# LoRa_SX1276_Shield.net
KiCad netlist of a schematic drawn in EAGLE
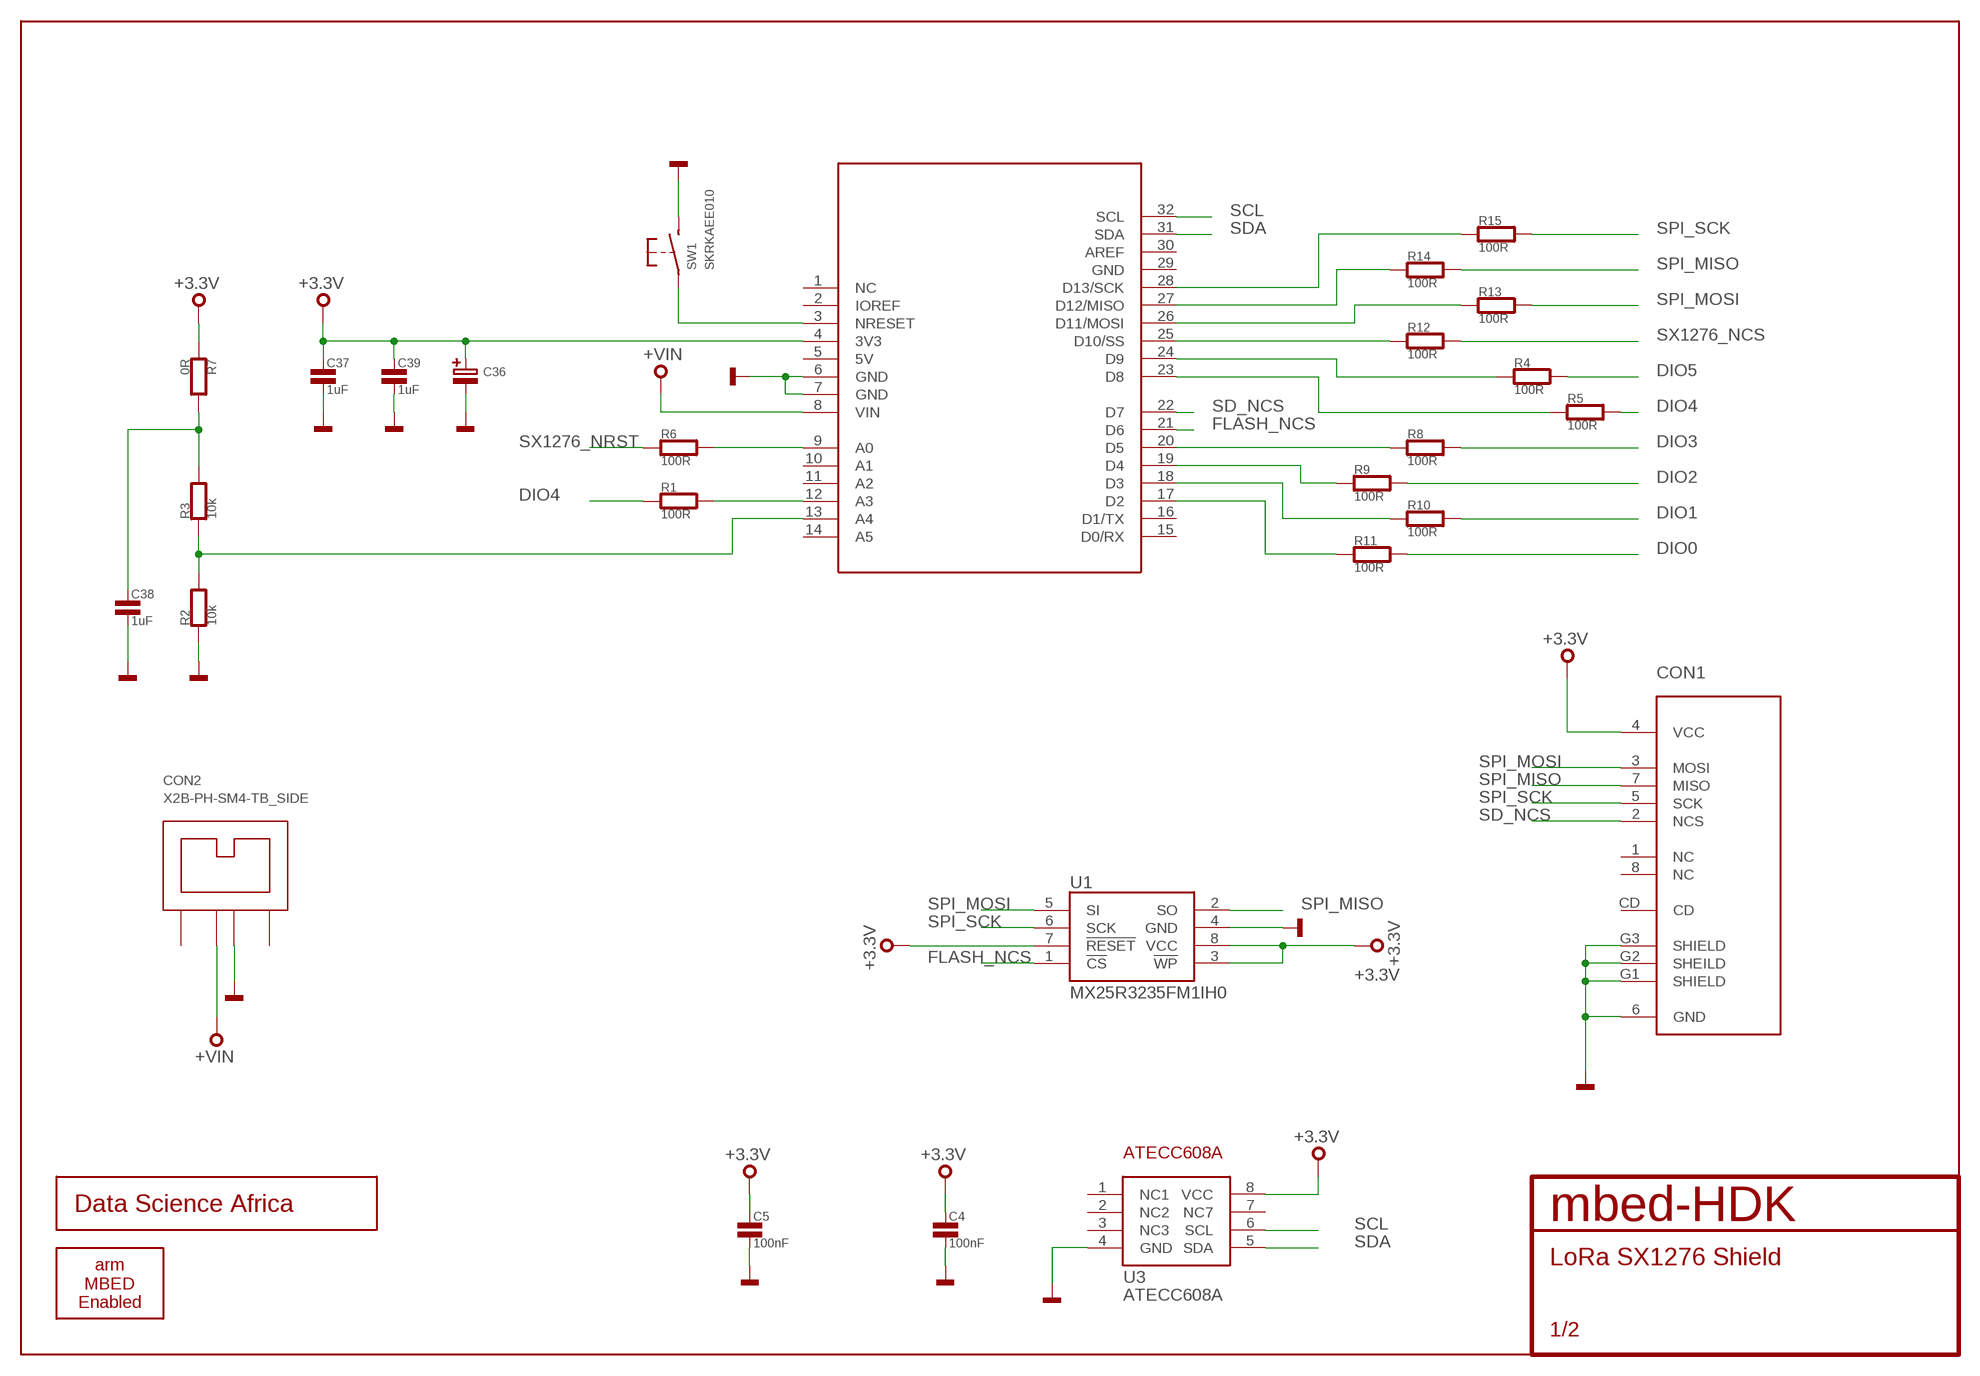
[diagram p0: schematic, sheet 1]
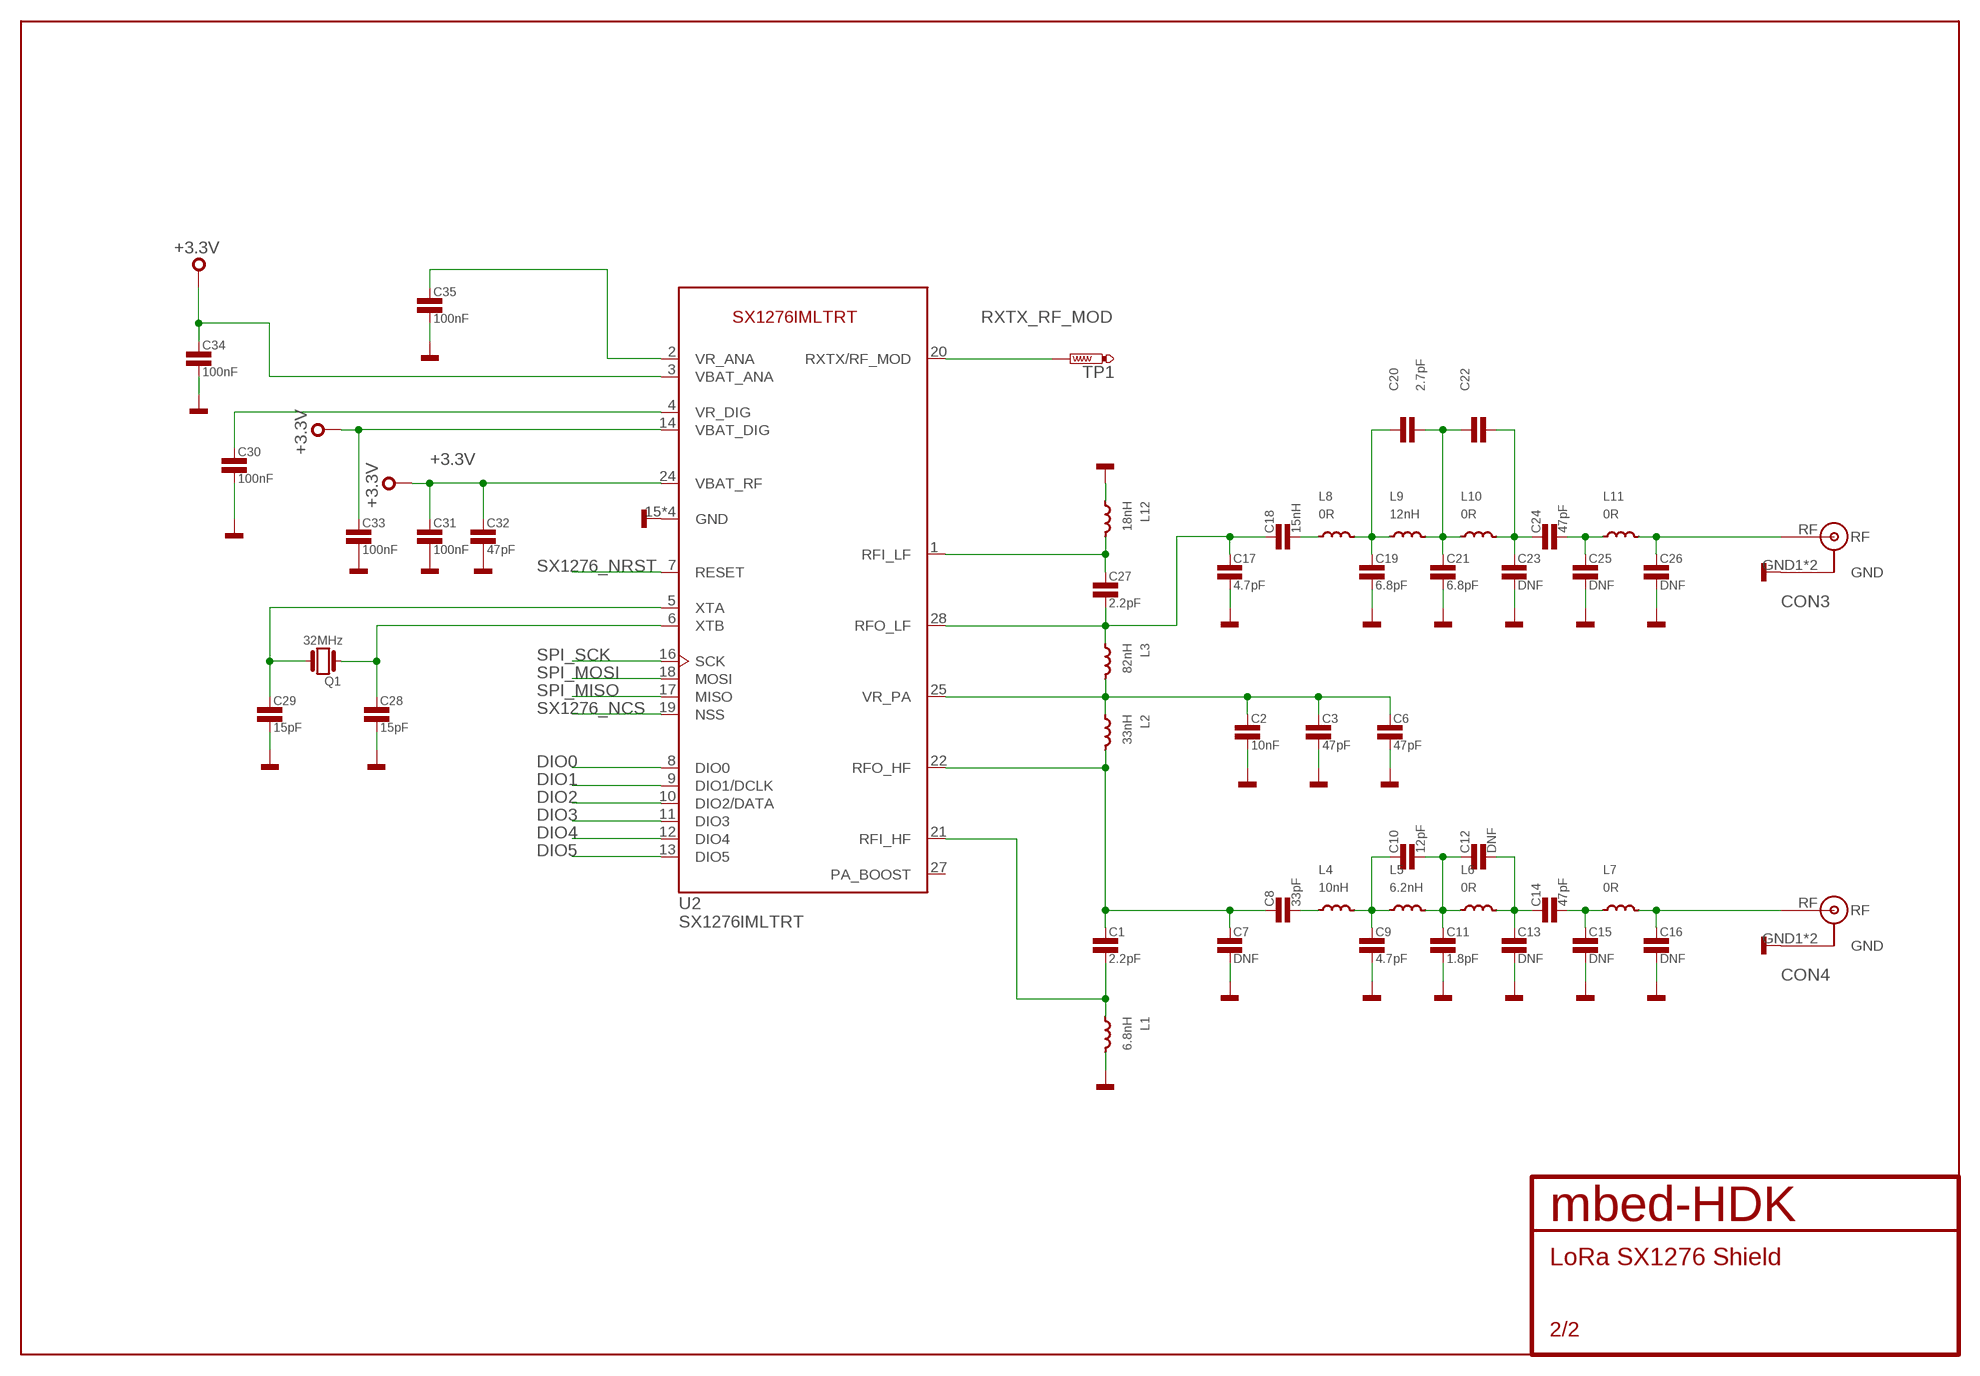
[diagram p1: schematic, sheet 2]

(export (version "E")
  (design (tool "Eeschema 10.0.6"))
  (components
    (comp (ref "C1")
      (value "2.2pF")
      (footprint "eagle-import:0402")
      (libsource (lib "eagle-import") (part "C0402"))
    )
    (comp (ref "C2")
      (value "10nF")
      (footprint "eagle-import:0402")
      (libsource (lib "eagle-import") (part "C0402"))
    )
    (comp (ref "C3")
      (value "47pF")
      (footprint "eagle-import:0402")
      (libsource (lib "eagle-import") (part "C0402"))
    )
    (comp (ref "C6")
      (value "47pF")
      (footprint "eagle-import:0402")
      (libsource (lib "eagle-import") (part "C0402"))
    )
    (comp (ref "C7")
      (value "DNF")
      (footprint "eagle-import:0402")
      (libsource (lib "eagle-import") (part "C0402"))
    )
    (comp (ref "C8")
      (value "33pF")
      (footprint "eagle-import:0402")
      (libsource (lib "eagle-import") (part "C0402"))
    )
    (comp (ref "C9")
      (value "4.7pF")
      (footprint "eagle-import:0402")
      (libsource (lib "eagle-import") (part "C0402"))
    )
    (comp (ref "C10")
      (value "12pF")
      (footprint "eagle-import:0402")
      (libsource (lib "eagle-import") (part "C0402"))
    )
    (comp (ref "C11")
      (value "1.8pF")
      (footprint "eagle-import:0402")
      (libsource (lib "eagle-import") (part "C0402"))
    )
    (comp (ref "C12")
      (value "DNF")
      (footprint "eagle-import:0402")
      (libsource (lib "eagle-import") (part "C0402"))
    )
    (comp (ref "C13")
      (value "DNF")
      (footprint "eagle-import:0402")
      (libsource (lib "eagle-import") (part "C0402"))
    )
    (comp (ref "C14")
      (value "47pF")
      (footprint "eagle-import:0402")
      (libsource (lib "eagle-import") (part "C0402"))
    )
    (comp (ref "C15")
      (value "DNF")
      (footprint "eagle-import:0402")
      (libsource (lib "eagle-import") (part "C0402"))
    )
    (comp (ref "C16")
      (value "DNF")
      (footprint "eagle-import:0402")
      (libsource (lib "eagle-import") (part "C0402"))
    )
    (comp (ref "C17")
      (value "4.7pF")
      (footprint "eagle-import:0402")
      (libsource (lib "eagle-import") (part "C0402"))
    )
    (comp (ref "C18")
      (value "15nH")
      (footprint "eagle-import:0402")
      (libsource (lib "eagle-import") (part "C0402"))
    )
    (comp (ref "C19")
      (value "6.8pF")
      (footprint "eagle-import:0402")
      (libsource (lib "eagle-import") (part "C0402"))
    )
    (comp (ref "C20")
      (value "2.7pF")
      (footprint "eagle-import:0402")
      (libsource (lib "eagle-import") (part "C0402"))
    )
    (comp (ref "C21")
      (value "6.8pF")
      (footprint "eagle-import:0402")
      (libsource (lib "eagle-import") (part "C0402"))
    )
    (comp (ref "C22")
      (value "C0402")
      (footprint "eagle-import:0402")
      (libsource (lib "eagle-import") (part "C0402"))
    )
    (comp (ref "C23")
      (value "DNF")
      (footprint "eagle-import:0402")
      (libsource (lib "eagle-import") (part "C0402"))
    )
    (comp (ref "C24")
      (value "47pF")
      (footprint "eagle-import:0402")
      (libsource (lib "eagle-import") (part "C0402"))
    )
    (comp (ref "C25")
      (value "DNF")
      (footprint "eagle-import:0402")
      (libsource (lib "eagle-import") (part "C0402"))
    )
    (comp (ref "C26")
      (value "DNF")
      (footprint "eagle-import:0402")
      (libsource (lib "eagle-import") (part "C0402"))
    )
    (comp (ref "C27")
      (value "2.2pF")
      (footprint "eagle-import:0402")
      (libsource (lib "eagle-import") (part "C0402"))
    )
    (comp (ref "C28")
      (value "15pF")
      (footprint "eagle-import:0402")
      (libsource (lib "eagle-import") (part "C0402"))
    )
    (comp (ref "C29")
      (value "15pF")
      (footprint "eagle-import:0402")
      (libsource (lib "eagle-import") (part "C0402"))
    )
    (comp (ref "C30")
      (value "100nF")
      (footprint "eagle-import:0402")
      (libsource (lib "eagle-import") (part "C0402"))
    )
    (comp (ref "C31")
      (value "100nF")
      (footprint "eagle-import:0402")
      (libsource (lib "eagle-import") (part "C0402"))
    )
    (comp (ref "C32")
      (value "47pF")
      (footprint "eagle-import:0402")
      (libsource (lib "eagle-import") (part "C0402"))
    )
    (comp (ref "C33")
      (value "100nF")
      (footprint "eagle-import:0402")
      (libsource (lib "eagle-import") (part "C0402"))
    )
    (comp (ref "C34")
      (value "100nF")
      (footprint "eagle-import:0402")
      (libsource (lib "eagle-import") (part "C0402"))
    )
    (comp (ref "C35")
      (value "100nF")
      (footprint "eagle-import:0402")
      (libsource (lib "eagle-import") (part "C0402"))
    )
    (comp (ref "CON3")
      (value "U.FL")
      (footprint "eagle-import:U.FL-R-SMT-1")
      (libsource (lib "eagle-import") (part "U.FL"))
    )
    (comp (ref "CON4")
      (value "U.FL")
      (footprint "eagle-import:U.FL-R-SMT-1")
      (libsource (lib "eagle-import") (part "U.FL"))
    )
    (comp (ref "L1")
      (value "6.8nH")
      (footprint "eagle-import:0402")
      (libsource (lib "eagle-import") (part "L0402"))
    )
    (comp (ref "L2")
      (value "33nH")
      (footprint "eagle-import:0402")
      (libsource (lib "eagle-import") (part "L0402"))
    )
    (comp (ref "L3")
      (value "82nH")
      (footprint "eagle-import:0402")
      (libsource (lib "eagle-import") (part "L0402"))
    )
    (comp (ref "L4")
      (value "10nH")
      (footprint "eagle-import:0402")
      (libsource (lib "eagle-import") (part "L0402"))
    )
    (comp (ref "L5")
      (value "6.2nH")
      (footprint "eagle-import:0402")
      (libsource (lib "eagle-import") (part "L0402"))
    )
    (comp (ref "L6")
      (value "0R")
      (footprint "eagle-import:0402")
      (libsource (lib "eagle-import") (part "L0402"))
    )
    (comp (ref "L7")
      (value "0R")
      (footprint "eagle-import:0402")
      (libsource (lib "eagle-import") (part "L0402"))
    )
    (comp (ref "L8")
      (value "0R")
      (footprint "eagle-import:0402")
      (libsource (lib "eagle-import") (part "L0402"))
    )
    (comp (ref "L9")
      (value "12nH")
      (footprint "eagle-import:0402")
      (libsource (lib "eagle-import") (part "L0402"))
    )
    (comp (ref "L10")
      (value "0R")
      (footprint "eagle-import:0402")
      (libsource (lib "eagle-import") (part "L0402"))
    )
    (comp (ref "L11")
      (value "0R")
      (footprint "eagle-import:0402")
      (libsource (lib "eagle-import") (part "L0402"))
    )
    (comp (ref "L12")
      (value "18nH")
      (footprint "eagle-import:0402")
      (libsource (lib "eagle-import") (part "L0402"))
    )
    (comp (ref "Q1")
      (value "32MHz")
      (footprint "eagle-import:3.2X.2.5")
      (libsource (lib "eagle-import") (part "GENERIC-CRYSTAL_3.2X2.5"))
    )
    (comp (ref "TP1")
      (value "PTR1TP12R")
      (footprint "eagle-import:TP12R")
      (libsource (lib "eagle-import") (part "PTR1TP12R"))
    )
    (comp (ref "U2")
      (value "SX1276IMLTRT")
      (footprint "eagle-import:QFN65P600X600X100-29N")
      (fields (field (name "MF") "Semtec"))
      (libsource (lib "eagle-import") (part "SX1276IMLTRT"))
    )
    (comp (ref "BRD2")
      (value "ARDUINO-R3_APPS")
      (footprint "eagle-import:ARDUINO-R3-APPS-SHEILD")
      (libsource (lib "eagle-import") (part "ARDUINO-R3_APPS"))
    )
    (comp (ref "C4")
      (value "100nF")
      (footprint "eagle-import:0402")
      (libsource (lib "eagle-import") (part "C0402"))
    )
    (comp (ref "C5")
      (value "100nF")
      (footprint "eagle-import:0402")
      (libsource (lib "eagle-import") (part "C0402"))
    )
    (comp (ref "C36")
      (value "C-POLB")
      (footprint "eagle-import:SMC_B")
      (fields (field (name "MF") "Kemet"))
      (libsource (lib "eagle-import") (part "C-POLB"))
    )
    (comp (ref "C37")
      (value "1uF")
      (footprint "eagle-import:0603")
      (libsource (lib "eagle-import") (part "C0603"))
    )
    (comp (ref "C38")
      (value "1uF")
      (footprint "eagle-import:0603")
      (libsource (lib "eagle-import") (part "C0603"))
    )
    (comp (ref "C39")
      (value "1uF")
      (footprint "eagle-import:0402")
      (libsource (lib "eagle-import") (part "C0402"))
    )
    (comp (ref "CON1")
      (value "101-00660-68-6")
      (footprint "eagle-import:AMPHENOL-101-00660-68-6")
      (fields (field (name "MF") "Amphenol "))
      (libsource (lib "eagle-import") (part "101-00660-68-6"))
    )
    (comp (ref "CON2")
      (value "X2B-PH-SM4-TB_SIDE")
      (footprint "eagle-import:S2B-PH-SM4-TB")
      (libsource (lib "eagle-import") (part "X2B-PH-SM4-TB_SIDE"))
    )
    (comp (ref "R1")
      (value "100R")
      (footprint "eagle-import:0402")
      (libsource (lib "eagle-import") (part "R0402"))
    )
    (comp (ref "R2")
      (value "10k")
      (footprint "eagle-import:0402")
      (libsource (lib "eagle-import") (part "R0402"))
    )
    (comp (ref "R3")
      (value "10k")
      (footprint "eagle-import:0402")
      (libsource (lib "eagle-import") (part "R0402"))
    )
    (comp (ref "R4")
      (value "100R")
      (footprint "eagle-import:0402")
      (libsource (lib "eagle-import") (part "R0402"))
    )
    (comp (ref "R5")
      (value "100R")
      (footprint "eagle-import:0402")
      (libsource (lib "eagle-import") (part "R0402"))
    )
    (comp (ref "R6")
      (value "100R")
      (footprint "eagle-import:0402")
      (libsource (lib "eagle-import") (part "R0402"))
    )
    (comp (ref "R7")
      (value "0R")
      (footprint "eagle-import:0402")
      (libsource (lib "eagle-import") (part "R0402"))
    )
    (comp (ref "R8")
      (value "100R")
      (footprint "eagle-import:0402")
      (libsource (lib "eagle-import") (part "R0402"))
    )
    (comp (ref "R9")
      (value "100R")
      (footprint "eagle-import:0402")
      (libsource (lib "eagle-import") (part "R0402"))
    )
    (comp (ref "R10")
      (value "100R")
      (footprint "eagle-import:0402")
      (libsource (lib "eagle-import") (part "R0402"))
    )
    (comp (ref "R11")
      (value "100R")
      (footprint "eagle-import:0402")
      (libsource (lib "eagle-import") (part "R0402"))
    )
    (comp (ref "R12")
      (value "100R")
      (footprint "eagle-import:0402")
      (libsource (lib "eagle-import") (part "R0402"))
    )
    (comp (ref "R13")
      (value "100R")
      (footprint "eagle-import:0402")
      (libsource (lib "eagle-import") (part "R0402"))
    )
    (comp (ref "R14")
      (value "100R")
      (footprint "eagle-import:0402")
      (libsource (lib "eagle-import") (part "R0402"))
    )
    (comp (ref "R15")
      (value "100R")
      (footprint "eagle-import:0402")
      (libsource (lib "eagle-import") (part "R0402"))
    )
    (comp (ref "SS1")
      (value "ARM-MBED-ENABLED-12MM")
      (footprint "eagle-import:ARM-MBED-ENABLED-12MM")
      (libsource (lib "eagle-import") (part "ARM-MBED-ENABLED-12MM"))
    )
    (comp (ref "SS2")
      (value "DATA-SCIENCE-AFRICA")
      (footprint "eagle-import:DATA-SCIENCE-AFRICA")
      (libsource (lib "eagle-import") (part "DATA-SCIENCE-AFRICA"))
    )
    (comp (ref "SW1")
      (value "SKRKAEE010")
      (footprint "eagle-import:SKRKAEE010")
      (fields (field (name "MF") "ALPS"))
      (libsource (lib "eagle-import") (part "SKRKAEE010"))
    )
    (comp (ref "U1")
      (value "MX25R3235FM1IH0")
      (footprint "eagle-import:SO8")
      (fields (field (name "MF") "Macronix"))
      (libsource (lib "eagle-import") (part "MX25R3235FM1IH0"))
    )
    (comp (ref "U3")
      (value "ATECC608A")
      (footprint "eagle-import:SO8")
      (libsource (lib "eagle-import") (part "ATECC608A"))
    )
  )
  (nets
    (net (code "1") (name "+3.3V") (class "Default")
      (node (ref "BRD2") (pin "4") (pinfunction "3V3_4") (pintype "bidirectional"))
      (node (ref "C31") (pin "1") (pinfunction "P$1_1") (pintype "passive"))
      (node (ref "C32") (pin "1") (pinfunction "P$1_1") (pintype "passive"))
      (node (ref "C33") (pin "1") (pinfunction "P$1_1") (pintype "passive"))
      (node (ref "C34") (pin "1") (pinfunction "P$1_1") (pintype "passive"))
      (node (ref "C36") (pin "+") (pinfunction "+_+") (pintype "passive"))
      (node (ref "C37") (pin "1") (pinfunction "P$1_1") (pintype "passive"))
      (node (ref "C39") (pin "1") (pinfunction "P$1_1") (pintype "passive"))
      (node (ref "C4") (pin "1") (pinfunction "P$1_1") (pintype "passive"))
      (node (ref "C5") (pin "1") (pinfunction "P$1_1") (pintype "passive"))
      (node (ref "CON1") (pin "4") (pinfunction "VCC_4") (pintype "bidirectional"))
      (node (ref "R7") (pin "1") (pinfunction "P$1_1") (pintype "passive"))
      (node (ref "U1") (pin "3") (pinfunction "~{WP}_3") (pintype "bidirectional"))
      (node (ref "U1") (pin "7") (pinfunction "~{RESET}_7") (pintype "bidirectional"))
      (node (ref "U1") (pin "8") (pinfunction "VCC_8") (pintype "bidirectional"))
      (node (ref "U2") (pin "14") (pinfunction "VBAT_DIG_14") (pintype "power_in"))
      (node (ref "U2") (pin "24") (pinfunction "VBAT_RF_24") (pintype "output"))
      (node (ref "U2") (pin "3") (pinfunction "VBAT_ANA_3") (pintype "power_in"))
      (node (ref "U3") (pin "8") (pinfunction "VCC_8") (pintype "bidirectional"))
    )
    (net (code "2") (name "+VIN") (class "Default")
      (node (ref "BRD2") (pin "8") (pinfunction "VIN_8") (pintype "bidirectional"))
      (node (ref "CON2") (pin "P$1") (pinfunction "P$1_P$1") (pintype "bidirectional"))
    )
    (net (code "3") (name "DIO0") (class "Default")
      (node (ref "R11") (pin "2") (pinfunction "P$2_2") (pintype "passive"))
      (node (ref "U2") (pin "8") (pinfunction "DIO0_8") (pintype "bidirectional"))
    )
    (net (code "4") (name "DIO1") (class "Default")
      (node (ref "R10") (pin "2") (pinfunction "P$2_2") (pintype "passive"))
      (node (ref "U2") (pin "9") (pinfunction "DIO1/DCLK_9") (pintype "bidirectional"))
    )
    (net (code "5") (name "DIO2") (class "Default")
      (node (ref "R9") (pin "2") (pinfunction "P$2_2") (pintype "passive"))
      (node (ref "U2") (pin "10") (pinfunction "DIO2/DATA_10") (pintype "bidirectional"))
    )
    (net (code "6") (name "DIO3") (class "Default")
      (node (ref "R8") (pin "2") (pinfunction "P$2_2") (pintype "passive"))
      (node (ref "U2") (pin "11") (pinfunction "DIO3_11") (pintype "bidirectional"))
    )
    (net (code "7") (name "DIO4") (class "Default")
      (node (ref "R1") (pin "1") (pinfunction "P$1_1") (pintype "passive"))
      (node (ref "R5") (pin "2") (pinfunction "P$2_2") (pintype "passive"))
      (node (ref "U2") (pin "12") (pinfunction "DIO4_12") (pintype "bidirectional"))
    )
    (net (code "8") (name "DIO5") (class "Default")
      (node (ref "R4") (pin "2") (pinfunction "P$2_2") (pintype "passive"))
      (node (ref "U2") (pin "13") (pinfunction "DIO5_13") (pintype "bidirectional"))
    )
    (net (code "9") (name "FLASH_NCS") (class "Default")
      (node (ref "BRD2") (pin "21") (pinfunction "D6_21") (pintype "bidirectional"))
      (node (ref "U1") (pin "1") (pinfunction "~{CS}_1") (pintype "bidirectional"))
    )
    (net (code "10") (name "GND") (class "Default")
      (node (ref "BRD2") (pin "6") (pinfunction "GND_6") (pintype "bidirectional"))
      (node (ref "BRD2") (pin "7") (pinfunction "GND_7") (pintype "bidirectional"))
      (node (ref "C11") (pin "2") (pinfunction "P$2_2") (pintype "passive"))
      (node (ref "C13") (pin "2") (pinfunction "P$2_2") (pintype "passive"))
      (node (ref "C15") (pin "2") (pinfunction "P$2_2") (pintype "passive"))
      (node (ref "C16") (pin "2") (pinfunction "P$2_2") (pintype "passive"))
      (node (ref "C17") (pin "2") (pinfunction "P$2_2") (pintype "passive"))
      (node (ref "C19") (pin "2") (pinfunction "P$2_2") (pintype "passive"))
      (node (ref "C2") (pin "2") (pinfunction "P$2_2") (pintype "passive"))
      (node (ref "C21") (pin "2") (pinfunction "P$2_2") (pintype "passive"))
      (node (ref "C23") (pin "2") (pinfunction "P$2_2") (pintype "passive"))
      (node (ref "C25") (pin "2") (pinfunction "P$2_2") (pintype "passive"))
      (node (ref "C26") (pin "2") (pinfunction "P$2_2") (pintype "passive"))
      (node (ref "C28") (pin "2") (pinfunction "P$2_2") (pintype "passive"))
      (node (ref "C29") (pin "2") (pinfunction "P$2_2") (pintype "passive"))
      (node (ref "C3") (pin "2") (pinfunction "P$2_2") (pintype "passive"))
      (node (ref "C30") (pin "2") (pinfunction "P$2_2") (pintype "passive"))
      (node (ref "C31") (pin "2") (pinfunction "P$2_2") (pintype "passive"))
      (node (ref "C32") (pin "2") (pinfunction "P$2_2") (pintype "passive"))
      (node (ref "C33") (pin "2") (pinfunction "P$2_2") (pintype "passive"))
      (node (ref "C34") (pin "2") (pinfunction "P$2_2") (pintype "passive"))
      (node (ref "C35") (pin "2") (pinfunction "P$2_2") (pintype "passive"))
      (node (ref "C36") (pin "-") (pinfunction "-_-") (pintype "passive"))
      (node (ref "C37") (pin "2") (pinfunction "P$2_2") (pintype "passive"))
      (node (ref "C38") (pin "2") (pinfunction "P$2_2") (pintype "passive"))
      (node (ref "C39") (pin "2") (pinfunction "P$2_2") (pintype "passive"))
      (node (ref "C4") (pin "2") (pinfunction "P$2_2") (pintype "passive"))
      (node (ref "C5") (pin "2") (pinfunction "P$2_2") (pintype "passive"))
      (node (ref "C6") (pin "2") (pinfunction "P$2_2") (pintype "passive"))
      (node (ref "C7") (pin "2") (pinfunction "P$2_2") (pintype "passive"))
      (node (ref "C9") (pin "2") (pinfunction "P$2_2") (pintype "passive"))
      (node (ref "CON1") (pin "6") (pinfunction "GND_6") (pintype "bidirectional"))
      (node (ref "CON1") (pin "G1") (pinfunction "SHIELD_G1") (pintype "bidirectional"))
      (node (ref "CON1") (pin "G2") (pinfunction "SHEILD_G2") (pintype "bidirectional"))
      (node (ref "CON1") (pin "G3") (pinfunction "SHIELD_G3") (pintype "bidirectional"))
      (node (ref "CON2") (pin "P$2") (pinfunction "P$2_P$2") (pintype "bidirectional"))
      (node (ref "CON3") (pin "GND1") (pinfunction "GND_GND1") (pintype "bidirectional"))
      (node (ref "CON3") (pin "GND2") (pinfunction "GND_GND2") (pintype "bidirectional"))
      (node (ref "CON4") (pin "GND1") (pinfunction "GND_GND1") (pintype "bidirectional"))
      (node (ref "CON4") (pin "GND2") (pinfunction "GND_GND2") (pintype "bidirectional"))
      (node (ref "L1") (pin "2") (pinfunction "P$2_2") (pintype "bidirectional"))
      (node (ref "L12") (pin "1") (pinfunction "P$1_1") (pintype "bidirectional"))
      (node (ref "R2") (pin "1") (pinfunction "P$1_1") (pintype "passive"))
      (node (ref "SW1") (pin "P$2") (pinfunction "S_P$2") (pintype "passive"))
      (node (ref "U1") (pin "4") (pinfunction "GND_4") (pintype "bidirectional"))
      (node (ref "U2") (pin "15") (pinfunction "GND_15") (pintype "power_in"))
      (node (ref "U2") (pin "23") (pinfunction "GND_23") (pintype "power_in"))
      (node (ref "U2") (pin "26") (pinfunction "GND_26") (pintype "power_in"))
      (node (ref "U2") (pin "29") (pinfunction "GND_29") (pintype "power_in"))
      (node (ref "U3") (pin "4") (pinfunction "GND_4") (pintype "bidirectional"))
    )
    (net (code "11") (name "Net-(BRD2-A0)") (class "Default")
      (node (ref "BRD2") (pin "9") (pinfunction "A0_9") (pintype "bidirectional"))
      (node (ref "R6") (pin "2") (pinfunction "P$2_2") (pintype "passive"))
    )
    (net (code "12") (name "Net-(BRD2-A3)") (class "Default")
      (node (ref "BRD2") (pin "12") (pinfunction "A3_12") (pintype "bidirectional"))
      (node (ref "R1") (pin "2") (pinfunction "P$2_2") (pintype "passive"))
    )
    (net (code "13") (name "Net-(BRD2-A4)") (class "Default")
      (node (ref "BRD2") (pin "13") (pinfunction "A4_13") (pintype "bidirectional"))
      (node (ref "R2") (pin "2") (pinfunction "P$2_2") (pintype "passive"))
      (node (ref "R3") (pin "1") (pinfunction "P$1_1") (pintype "passive"))
    )
    (net (code "14") (name "Net-(BRD2-D2)") (class "Default")
      (node (ref "BRD2") (pin "17") (pinfunction "D2_17") (pintype "bidirectional"))
      (node (ref "R11") (pin "1") (pinfunction "P$1_1") (pintype "passive"))
    )
    (net (code "15") (name "Net-(BRD2-D3)") (class "Default")
      (node (ref "BRD2") (pin "18") (pinfunction "D3_18") (pintype "bidirectional"))
      (node (ref "R10") (pin "1") (pinfunction "P$1_1") (pintype "passive"))
    )
    (net (code "16") (name "Net-(BRD2-D4)") (class "Default")
      (node (ref "BRD2") (pin "19") (pinfunction "D4_19") (pintype "bidirectional"))
      (node (ref "R9") (pin "1") (pinfunction "P$1_1") (pintype "passive"))
    )
    (net (code "17") (name "Net-(BRD2-D5)") (class "Default")
      (node (ref "BRD2") (pin "20") (pinfunction "D5_20") (pintype "bidirectional"))
      (node (ref "R8") (pin "1") (pinfunction "P$1_1") (pintype "passive"))
    )
    (net (code "18") (name "Net-(BRD2-D8)") (class "Default")
      (node (ref "BRD2") (pin "23") (pinfunction "D8_23") (pintype "bidirectional"))
      (node (ref "R5") (pin "1") (pinfunction "P$1_1") (pintype "passive"))
    )
    (net (code "19") (name "Net-(BRD2-D9)") (class "Default")
      (node (ref "BRD2") (pin "24") (pinfunction "D9_24") (pintype "bidirectional"))
      (node (ref "R4") (pin "1") (pinfunction "P$1_1") (pintype "passive"))
    )
    (net (code "20") (name "Net-(BRD2-D10{slash}SS)") (class "Default")
      (node (ref "BRD2") (pin "25") (pinfunction "D10/SS_25") (pintype "bidirectional"))
      (node (ref "R12") (pin "1") (pinfunction "P$1_1") (pintype "passive"))
    )
    (net (code "21") (name "Net-(BRD2-D11{slash}MOSI)") (class "Default")
      (node (ref "BRD2") (pin "26") (pinfunction "D11/MOSI_26") (pintype "bidirectional"))
      (node (ref "R13") (pin "1") (pinfunction "P$1_1") (pintype "passive"))
    )
    (net (code "22") (name "Net-(BRD2-D12{slash}MISO)") (class "Default")
      (node (ref "BRD2") (pin "27") (pinfunction "D12/MISO_27") (pintype "bidirectional"))
      (node (ref "R14") (pin "1") (pinfunction "P$1_1") (pintype "passive"))
    )
    (net (code "23") (name "Net-(BRD2-D13{slash}SCK)") (class "Default")
      (node (ref "BRD2") (pin "28") (pinfunction "D13/SCK_28") (pintype "bidirectional"))
      (node (ref "R15") (pin "1") (pinfunction "P$1_1") (pintype "passive"))
    )
    (net (code "24") (name "Net-(BRD2-NRESET)") (class "Default")
      (node (ref "BRD2") (pin "3") (pinfunction "NRESET_3") (pintype "bidirectional"))
      (node (ref "SW1") (pin "P$1") (pinfunction "P_P$1") (pintype "passive"))
    )
    (net (code "25") (name "Net-(C1-P$1)") (class "Default")
      (node (ref "C1") (pin "1") (pinfunction "P$1_1") (pintype "passive"))
      (node (ref "C7") (pin "1") (pinfunction "P$1_1") (pintype "passive"))
      (node (ref "C8") (pin "1") (pinfunction "P$1_1") (pintype "passive"))
      (node (ref "L2") (pin "2") (pinfunction "P$2_2") (pintype "bidirectional"))
      (node (ref "U2") (pin "22") (pinfunction "RFO_HF_22") (pintype "output"))
    )
    (net (code "26") (name "Net-(C1-P$2)") (class "Default")
      (node (ref "C1") (pin "2") (pinfunction "P$2_2") (pintype "passive"))
      (node (ref "L1") (pin "1") (pinfunction "P$1_1") (pintype "bidirectional"))
      (node (ref "U2") (pin "21") (pinfunction "RFI_HF_21") (pintype "input"))
    )
    (net (code "27") (name "Net-(C2-P$1)") (class "Default")
      (node (ref "C2") (pin "1") (pinfunction "P$1_1") (pintype "passive"))
      (node (ref "C3") (pin "1") (pinfunction "P$1_1") (pintype "passive"))
      (node (ref "C6") (pin "1") (pinfunction "P$1_1") (pintype "passive"))
      (node (ref "L2") (pin "1") (pinfunction "P$1_1") (pintype "bidirectional"))
      (node (ref "L3") (pin "2") (pinfunction "P$2_2") (pintype "bidirectional"))
      (node (ref "U2") (pin "25") (pinfunction "VR_PA_25") (pintype "output"))
    )
    (net (code "28") (name "Net-(C8-P$2)") (class "Default")
      (node (ref "C8") (pin "2") (pinfunction "P$2_2") (pintype "passive"))
      (node (ref "L4") (pin "1") (pinfunction "P$1_1") (pintype "bidirectional"))
    )
    (net (code "29") (name "Net-(C10-P$1)") (class "Default")
      (node (ref "C10") (pin "1") (pinfunction "P$1_1") (pintype "passive"))
      (node (ref "C9") (pin "1") (pinfunction "P$1_1") (pintype "passive"))
      (node (ref "L4") (pin "2") (pinfunction "P$2_2") (pintype "bidirectional"))
      (node (ref "L5") (pin "1") (pinfunction "P$1_1") (pintype "bidirectional"))
    )
    (net (code "30") (name "Net-(C10-P$2)") (class "Default")
      (node (ref "C10") (pin "2") (pinfunction "P$2_2") (pintype "passive"))
      (node (ref "C11") (pin "1") (pinfunction "P$1_1") (pintype "passive"))
      (node (ref "C12") (pin "1") (pinfunction "P$1_1") (pintype "passive"))
      (node (ref "L5") (pin "2") (pinfunction "P$2_2") (pintype "bidirectional"))
      (node (ref "L6") (pin "1") (pinfunction "P$1_1") (pintype "bidirectional"))
    )
    (net (code "31") (name "Net-(C12-P$2)") (class "Default")
      (node (ref "C12") (pin "2") (pinfunction "P$2_2") (pintype "passive"))
      (node (ref "C13") (pin "1") (pinfunction "P$1_1") (pintype "passive"))
      (node (ref "C14") (pin "1") (pinfunction "P$1_1") (pintype "passive"))
      (node (ref "L6") (pin "2") (pinfunction "P$2_2") (pintype "bidirectional"))
    )
    (net (code "32") (name "Net-(C14-P$2)") (class "Default")
      (node (ref "C14") (pin "2") (pinfunction "P$2_2") (pintype "passive"))
      (node (ref "C15") (pin "1") (pinfunction "P$1_1") (pintype "passive"))
      (node (ref "L7") (pin "1") (pinfunction "P$1_1") (pintype "bidirectional"))
    )
    (net (code "33") (name "Net-(C16-P$1)") (class "Default")
      (node (ref "C16") (pin "1") (pinfunction "P$1_1") (pintype "passive"))
      (node (ref "CON4") (pin "RF") (pinfunction "RF_RF") (pintype "bidirectional"))
      (node (ref "L7") (pin "2") (pinfunction "P$2_2") (pintype "bidirectional"))
    )
    (net (code "34") (name "Net-(C17-P$1)") (class "Default")
      (node (ref "C17") (pin "1") (pinfunction "P$1_1") (pintype "passive"))
      (node (ref "C18") (pin "1") (pinfunction "P$1_1") (pintype "passive"))
      (node (ref "C27") (pin "2") (pinfunction "P$2_2") (pintype "passive"))
      (node (ref "L3") (pin "1") (pinfunction "P$1_1") (pintype "bidirectional"))
      (node (ref "U2") (pin "28") (pinfunction "RFO_LF_28") (pintype "output"))
    )
    (net (code "35") (name "Net-(C18-P$2)") (class "Default")
      (node (ref "C18") (pin "2") (pinfunction "P$2_2") (pintype "passive"))
      (node (ref "L8") (pin "1") (pinfunction "P$1_1") (pintype "bidirectional"))
    )
    (net (code "36") (name "Net-(C19-P$1)") (class "Default")
      (node (ref "C19") (pin "1") (pinfunction "P$1_1") (pintype "passive"))
      (node (ref "C20") (pin "1") (pinfunction "P$1_1") (pintype "passive"))
      (node (ref "L8") (pin "2") (pinfunction "P$2_2") (pintype "bidirectional"))
      (node (ref "L9") (pin "1") (pinfunction "P$1_1") (pintype "bidirectional"))
    )
    (net (code "37") (name "Net-(C20-P$2)") (class "Default")
      (node (ref "C20") (pin "2") (pinfunction "P$2_2") (pintype "passive"))
      (node (ref "C21") (pin "1") (pinfunction "P$1_1") (pintype "passive"))
      (node (ref "C22") (pin "1") (pinfunction "P$1_1") (pintype "passive"))
      (node (ref "L10") (pin "1") (pinfunction "P$1_1") (pintype "bidirectional"))
      (node (ref "L9") (pin "2") (pinfunction "P$2_2") (pintype "bidirectional"))
    )
    (net (code "38") (name "Net-(C22-P$2)") (class "Default")
      (node (ref "C22") (pin "2") (pinfunction "P$2_2") (pintype "passive"))
      (node (ref "C23") (pin "1") (pinfunction "P$1_1") (pintype "passive"))
      (node (ref "C24") (pin "1") (pinfunction "P$1_1") (pintype "passive"))
      (node (ref "L10") (pin "2") (pinfunction "P$2_2") (pintype "bidirectional"))
    )
    (net (code "39") (name "Net-(C24-P$2)") (class "Default")
      (node (ref "C24") (pin "2") (pinfunction "P$2_2") (pintype "passive"))
      (node (ref "C25") (pin "1") (pinfunction "P$1_1") (pintype "passive"))
      (node (ref "L11") (pin "1") (pinfunction "P$1_1") (pintype "bidirectional"))
    )
    (net (code "40") (name "Net-(C26-P$1)") (class "Default")
      (node (ref "C26") (pin "1") (pinfunction "P$1_1") (pintype "passive"))
      (node (ref "CON3") (pin "RF") (pinfunction "RF_RF") (pintype "bidirectional"))
      (node (ref "L11") (pin "2") (pinfunction "P$2_2") (pintype "bidirectional"))
    )
    (net (code "41") (name "Net-(C27-P$1)") (class "Default")
      (node (ref "C27") (pin "1") (pinfunction "P$1_1") (pintype "passive"))
      (node (ref "L12") (pin "2") (pinfunction "P$2_2") (pintype "bidirectional"))
      (node (ref "U2") (pin "1") (pinfunction "RFI_LF_1") (pintype "input"))
    )
    (net (code "42") (name "Net-(C28-P$1)") (class "Default")
      (node (ref "C28") (pin "1") (pinfunction "P$1_1") (pintype "passive"))
      (node (ref "Q1") (pin "P$1") (pinfunction "1_P$1") (pintype "passive"))
      (node (ref "U2") (pin "6") (pinfunction "XTB_6") (pintype "bidirectional"))
    )
    (net (code "43") (name "Net-(C29-P$1)") (class "Default")
      (node (ref "C29") (pin "1") (pinfunction "P$1_1") (pintype "passive"))
      (node (ref "Q1") (pin "P$3") (pinfunction "2_P$3") (pintype "passive"))
      (node (ref "U2") (pin "5") (pinfunction "XTA_5") (pintype "bidirectional"))
    )
    (net (code "44") (name "Net-(C30-P$1)") (class "Default")
      (node (ref "C30") (pin "1") (pinfunction "P$1_1") (pintype "passive"))
      (node (ref "U2") (pin "4") (pinfunction "VR_DIG_4") (pintype "power_in"))
    )
    (net (code "45") (name "Net-(C35-P$1)") (class "Default")
      (node (ref "C35") (pin "1") (pinfunction "P$1_1") (pintype "passive"))
      (node (ref "U2") (pin "2") (pinfunction "VR_ANA_2") (pintype "power_in"))
    )
    (net (code "46") (name "Net-(C38-P$1)") (class "Default")
      (node (ref "C38") (pin "1") (pinfunction "P$1_1") (pintype "passive"))
      (node (ref "R3") (pin "2") (pinfunction "P$2_2") (pintype "passive"))
      (node (ref "R7") (pin "2") (pinfunction "P$2_2") (pintype "passive"))
    )
    (net (code "47") (name "RXTX_RF_MOD") (class "Default")
      (node (ref "TP1") (pin "TP") (pinfunction "TP_TP") (pintype "input"))
      (node (ref "U2") (pin "20") (pinfunction "RXTX/RF_MOD_20") (pintype "output"))
    )
    (net (code "48") (name "SCL") (class "Default")
      (node (ref "BRD2") (pin "32") (pinfunction "SCL_32") (pintype "bidirectional"))
      (node (ref "U3") (pin "6") (pinfunction "SCL_6") (pintype "bidirectional"))
    )
    (net (code "49") (name "SDA") (class "Default")
      (node (ref "BRD2") (pin "31") (pinfunction "SDA_31") (pintype "bidirectional"))
      (node (ref "U3") (pin "5") (pinfunction "SDA_5") (pintype "bidirectional"))
    )
    (net (code "50") (name "SD_NCS") (class "Default")
      (node (ref "BRD2") (pin "22") (pinfunction "D7_22") (pintype "bidirectional"))
      (node (ref "CON1") (pin "2") (pinfunction "NCS_2") (pintype "bidirectional"))
    )
    (net (code "51") (name "SPI_MISO") (class "Default")
      (node (ref "CON1") (pin "7") (pinfunction "MISO_7") (pintype "bidirectional"))
      (node (ref "R14") (pin "2") (pinfunction "P$2_2") (pintype "passive"))
      (node (ref "U1") (pin "2") (pinfunction "SO_2") (pintype "bidirectional"))
      (node (ref "U2") (pin "17") (pinfunction "MISO_17") (pintype "output"))
    )
    (net (code "52") (name "SPI_MOSI") (class "Default")
      (node (ref "CON1") (pin "3") (pinfunction "MOSI_3") (pintype "bidirectional"))
      (node (ref "R13") (pin "2") (pinfunction "P$2_2") (pintype "passive"))
      (node (ref "U1") (pin "5") (pinfunction "SI_5") (pintype "bidirectional"))
      (node (ref "U2") (pin "18") (pinfunction "MOSI_18") (pintype "input"))
    )
    (net (code "53") (name "SPI_SCK") (class "Default")
      (node (ref "CON1") (pin "5") (pinfunction "SCK_5") (pintype "bidirectional"))
      (node (ref "R15") (pin "2") (pinfunction "P$2_2") (pintype "passive"))
      (node (ref "U1") (pin "6") (pinfunction "SCK_6") (pintype "bidirectional"))
      (node (ref "U2") (pin "16") (pinfunction "SCK_16") (pintype "input"))
    )
    (net (code "54") (name "SX1276_NCS") (class "Default")
      (node (ref "R12") (pin "2") (pinfunction "P$2_2") (pintype "passive"))
      (node (ref "U2") (pin "19") (pinfunction "NSS_19") (pintype "input"))
    )
    (net (code "55") (name "SX1276_NRST") (class "Default")
      (node (ref "R6") (pin "1") (pinfunction "P$1_1") (pintype "passive"))
      (node (ref "U2") (pin "7") (pinfunction "RESET_7") (pintype "bidirectional"))
    )
    (net (code "56") (name "unconnected-(BRD2-5V-Pad5)") (class "Default")
      (node (ref "BRD2") (pin "5") (pinfunction "5V_5") (pintype "bidirectional"))
    )
    (net (code "57") (name "unconnected-(BRD2-A1-Pad10)") (class "Default")
      (node (ref "BRD2") (pin "10") (pinfunction "A1_10") (pintype "bidirectional"))
    )
    (net (code "58") (name "unconnected-(BRD2-A2-Pad11)") (class "Default")
      (node (ref "BRD2") (pin "11") (pinfunction "A2_11") (pintype "bidirectional"))
    )
    (net (code "59") (name "unconnected-(BRD2-A5-Pad14)") (class "Default")
      (node (ref "BRD2") (pin "14") (pinfunction "A5_14") (pintype "bidirectional"))
    )
    (net (code "60") (name "unconnected-(BRD2-AREF-Pad30)") (class "Default")
      (node (ref "BRD2") (pin "30") (pinfunction "AREF_30") (pintype "bidirectional"))
    )
    (net (code "61") (name "unconnected-(BRD2-D0{slash}RX-Pad15)") (class "Default")
      (node (ref "BRD2") (pin "15") (pinfunction "D0/RX_15") (pintype "bidirectional"))
    )
    (net (code "62") (name "unconnected-(BRD2-D1{slash}TX-Pad16)") (class "Default")
      (node (ref "BRD2") (pin "16") (pinfunction "D1/TX_16") (pintype "bidirectional"))
    )
    (net (code "63") (name "unconnected-(BRD2-GND-Pad29)") (class "Default")
      (node (ref "BRD2") (pin "29") (pinfunction "GND_29") (pintype "bidirectional"))
    )
    (net (code "64") (name "unconnected-(BRD2-IOREF-Pad2)") (class "Default")
      (node (ref "BRD2") (pin "2") (pinfunction "IOREF_2") (pintype "bidirectional"))
    )
    (net (code "65") (name "unconnected-(BRD2-NC-Pad1)") (class "Default")
      (node (ref "BRD2") (pin "1") (pinfunction "NC_1") (pintype "bidirectional"))
    )
    (net (code "66") (name "unconnected-(CON1-NC-Pad1)") (class "Default")
      (node (ref "CON1") (pin "1") (pinfunction "NC_1") (pintype "bidirectional"))
    )
    (net (code "67") (name "unconnected-(CON1-NC-Pad8)") (class "Default")
      (node (ref "CON1") (pin "8") (pinfunction "NC_8") (pintype "bidirectional"))
    )
    (net (code "68") (name "unconnected-(CON1-PadCD)") (class "Default")
      (node (ref "CON1") (pin "CD") (pinfunction "CD_CD") (pintype "bidirectional"))
    )
    (net (code "69") (name "unconnected-(CON2-PadG1)") (class "Default")
      (node (ref "CON2") (pin "G1") (pinfunction "G1_G1") (pintype "bidirectional"))
    )
    (net (code "70") (name "unconnected-(CON2-PadG2)") (class "Default")
      (node (ref "CON2") (pin "G2") (pinfunction "G2_G2") (pintype "bidirectional"))
    )
    (net (code "71") (name "unconnected-(U2-PA_BOOST-Pad27)") (class "Default")
      (node (ref "U2") (pin "27") (pinfunction "PA_BOOST_27") (pintype "output"))
    )
    (net (code "72") (name "unconnected-(U3-NC1-Pad1)") (class "Default")
      (node (ref "U3") (pin "1") (pinfunction "NC1_1") (pintype "bidirectional"))
    )
    (net (code "73") (name "unconnected-(U3-NC2-Pad2)") (class "Default")
      (node (ref "U3") (pin "2") (pinfunction "NC2_2") (pintype "bidirectional"))
    )
    (net (code "74") (name "unconnected-(U3-NC3-Pad3)") (class "Default")
      (node (ref "U3") (pin "3") (pinfunction "NC3_3") (pintype "bidirectional"))
    )
    (net (code "75") (name "unconnected-(U3-NC7-Pad7)") (class "Default")
      (node (ref "U3") (pin "7") (pinfunction "NC7_7") (pintype "bidirectional"))
    )
  )
)
